# SH_SW1_V1_0.net
KiCad netlist of a schematic drawn in Altium Designer
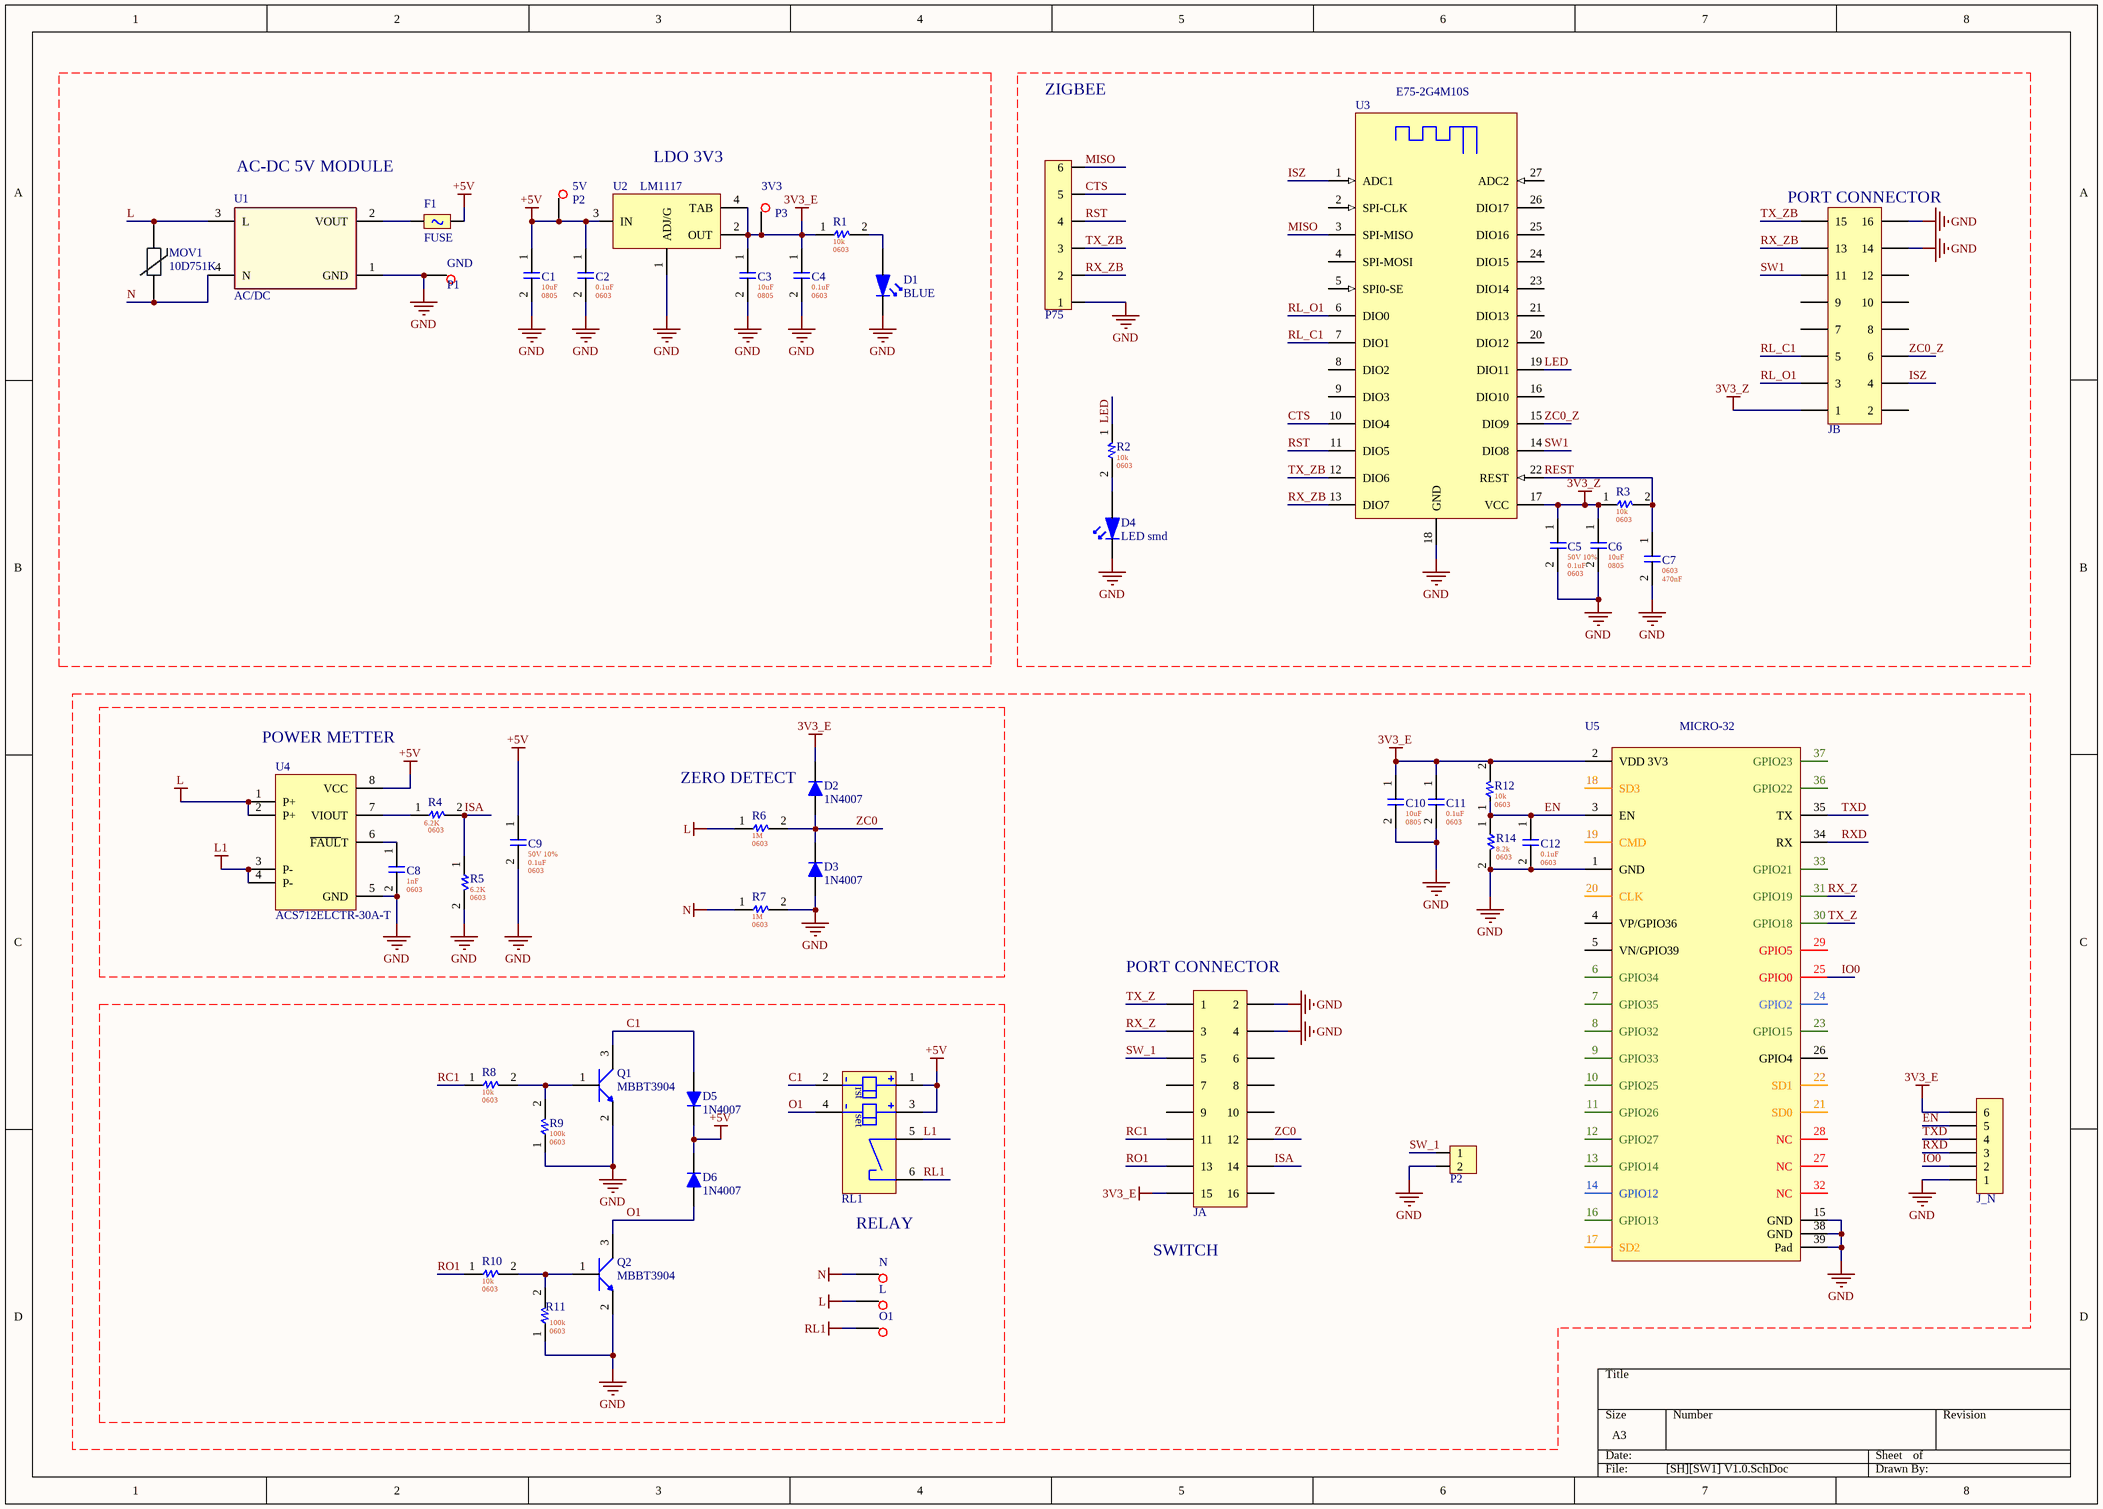
[diagram p0: [SH][SW1] V1.0.SchDoc]

(export (version "E")
  (design (tool "Eeschema 10.0.6"))
  (components
    (comp (ref "3V3") (value "P3") (footprint "TEXT_POINT") (libsource (lib "Kienlib") (part "P1")))
    (comp (ref "5V") (value "P2") (footprint "TEXT_POINT") (libsource (lib "Kienlib") (part "P1")))
    (comp (ref "C1")
      (value "10uF")
      (footprint "0805 C")
      (description "CAP CER 10uF 50V 10% 0805 SMD")
      (fields (field (name "FP") "0805") (field (name "CREATOR") "MMUOP"))
      (libsource (lib "Capacitor") (part "0805 10uF CER"))
    )
    (comp (ref "C2")
      (value "0.1uF")
      (footprint "0603 C")
      (description "CAP CER 0.1uF 50V 10% 0603 SMD")
      (fields (field (name "FP") "0603") (field (name "CREATOR") "MMUOP"))
      (libsource (lib "Capacitor") (part "0603 0.1uF CER"))
    )
    (comp (ref "C3")
      (value "10uF")
      (footprint "0805 C")
      (description "CAP CER 10uF 50V 10% 0805 SMD")
      (fields (field (name "FP") "0805") (field (name "CREATOR") "MMUOP"))
      (libsource (lib "Capacitor") (part "0805 10uF CER"))
    )
    (comp (ref "C4")
      (value "0.1uF")
      (footprint "0603 C")
      (description "CAP CER 0.1uF 50V 10% 0603 SMD")
      (fields (field (name "FP") "0603") (field (name "CREATOR") "MMUOP"))
      (libsource (lib "Capacitor") (part "0603 0.1uF CER"))
    )
    (comp (ref "C5")
      (value "0.1uF")
      (footprint "0603 C")
      (description "CAP CER 0.1uF 50V 10% 0603 SMD")
      (fields
        (field (name "VOLTAGE + TOLE") "50V 10%")
        (field (name "FP") "0603")
        (field (name "CREATOR") "MMUOP")
      )
      (libsource (lib "Capacitor") (part "0603 0.1uF CER"))
    )
    (comp (ref "C6")
      (value "10uF")
      (footprint "0805 C")
      (description "CAP CER 10uF 50V 10% 0805 SMD")
      (fields (field (name "FP") "0805") (field (name "CREATOR") "MMUOP"))
      (libsource (lib "Capacitor") (part "0805 10uF CER"))
    )
    (comp (ref "C7")
      (value "470nF")
      (footprint "0603 C")
      (description "CAP CER 470nF 50V 10% 0603 SMD")
      (fields (field (name "FP") "0603") (field (name "CREATOR") "MMUOP"))
      (libsource (lib "Capacitor") (part "0603 470nF CER"))
    )
    (comp (ref "C8")
      (value "1nF")
      (footprint "0603 C")
      (description "CAP CER 1nF 50V 10% 0603 SMD")
      (fields (field (name "FP") "0603") (field (name "CREATOR") "MMUOP"))
      (libsource (lib "Capacitor") (part "0603 1nF CER"))
    )
    (comp (ref "C9")
      (value "0.1uF")
      (footprint "0603 C")
      (description "CAP CER 0.1uF 50V 10% 0603 SMD")
      (fields
        (field (name "VOLTAGE + TOLE") "50V 10%")
        (field (name "FP") "0603")
        (field (name "CREATOR") "MMUOP")
      )
      (libsource (lib "Capacitor") (part "0603 0.1uF CER"))
    )
    (comp (ref "C10")
      (value "10uF")
      (footprint "0805 C")
      (description "CAP CER 10uF 50V 10% 0805 SMD")
      (fields (field (name "FP") "0805") (field (name "CREATOR") "MMUOP"))
      (libsource (lib "Capacitor") (part "0805 10uF CER"))
    )
    (comp (ref "C11")
      (value "0.1uF")
      (footprint "0603 C")
      (description "CAP CER 0.1uF 50V 10% 0603 SMD")
      (fields (field (name "FP") "0603") (field (name "CREATOR") "MMUOP"))
      (libsource (lib "Capacitor") (part "0603 0.1uF CER"))
    )
    (comp (ref "C12")
      (value "0.1uF")
      (footprint "0603 C")
      (description "CAP CER 0.1uF 50V 10% 0603 SMD")
      (fields (field (name "FP") "0603") (field (name "CREATOR") "MMUOP"))
      (libsource (lib "Capacitor") (part "0603 0.1uF CER"))
    )
    (comp (ref "D1") (value "BLUE") (footprint "Led 1206") (libsource (lib "Kienlib") (part "LED smd")))
    (comp (ref "D2")
      (value "1N4007")
      (footprint "SOD-123")
      (libsource (lib "Kienlib") (part "Diode schottky"))
    )
    (comp (ref "D3")
      (value "1N4007")
      (footprint "SOD-123")
      (libsource (lib "Kienlib") (part "Diode schottky"))
    )
    (comp (ref "D4") (value "LED smd") (footprint "Led 1206") (libsource (lib "Kienlib") (part "LED smd")))
    (comp (ref "D5")
      (value "1N4007")
      (footprint "SOD-123")
      (libsource (lib "Kienlib") (part "Diode schottky"))
    )
    (comp (ref "D6")
      (value "1N4007")
      (footprint "SOD-123")
      (libsource (lib "Kienlib") (part "Diode schottky"))
    )
    (comp (ref "F1") (value "FUSE") (footprint "1812") (libsource (lib "Kienlib") (part "FUSE")))
    (comp (ref "GND") (value "P1") (footprint "TEXT_POINT") (libsource (lib "Kienlib") (part "P1")))
    (comp (ref "JA")
      (value "rao doi")
      (footprint "P2X8 - 2.0mm - female - SMD")
      (libsource (lib "Kienlib") (part "P2x8"))
    )
    (comp (ref "JB") (value "rao doi") (footprint "P2X8 - 2.0mm - SMD") (libsource (lib "") (part "P2x8_1")))
    (comp (ref "J_N") (value "P6") (footprint "P6 - 1.27MM") (libsource (lib "Kienlib") (part "P6")))
    (comp (ref "L") (value "P1") (footprint "P1 - BRASS TERMINAL") (libsource (lib "Kienlib") (part "P1")))
    (comp (ref "MOV1")
      (value "10D751K")
      (footprint "MOV")
      (description "750V")
      (libsource (lib "Kienlib") (part "VARISTOR"))
    )
    (comp (ref "N") (value "P1") (footprint "P1 - BRASS TERMINAL") (libsource (lib "Kienlib") (part "P1")))
    (comp (ref "O1") (value "P1") (footprint "P1 - BRASS TERMINAL") (libsource (lib "Kienlib") (part "P1")))
    (comp (ref "P2") (value "P2") (footprint "P2 - 2.54mm") (libsource (lib "Kienlib") (part "P2")))
    (comp (ref "P75") (value "P6") (footprint "P6 - 1.27MM") (libsource (lib "") (part "P6_1")))
    (comp (ref "Q1")
      (value "MBBT3904")
      (footprint "SOT 23-3")
      (description "Bipolar (BJT) Transistor NPN 40 V 200 mA 300MHz 350 mW Surface Mount SOT-23-3 (TO-236)")
      (libsource (lib "Kienlib") (part "TRANS NPN"))
    )
    (comp (ref "Q2")
      (value "MBBT3904")
      (footprint "SOT 23-3")
      (description "Bipolar (BJT) Transistor NPN 40 V 200 mA 300MHz 350 mW Surface Mount SOT-23-3 (TO-236)")
      (libsource (lib "Kienlib") (part "TRANS NPN"))
    )
    (comp (ref "R1")
      (value "10k")
      (footprint "0603 R")
      (description "10k 1% 0603 SMD")
      (fields (field (name "FP") "0603") (field (name "CREATOR") "MMUOP"))
      (libsource (lib "Res") (part "0603 10k 1%"))
    )
    (comp (ref "R2")
      (value "10k")
      (footprint "0603 R")
      (description "10k 1% 0603 SMD")
      (fields (field (name "FP") "0603") (field (name "CREATOR") "MMUOP"))
      (libsource (lib "Res") (part "0603 10k 1%"))
    )
    (comp (ref "R3")
      (value "10k")
      (footprint "0603 R")
      (description "10k 1% 0603 SMD")
      (fields (field (name "FP") "0603") (field (name "CREATOR") "MMUOP"))
      (libsource (lib "Res") (part "0603 10k 1%"))
    )
    (comp (ref "R4")
      (value "6.2K")
      (footprint "0603 R")
      (description "8.2k 1% 0603 SMD")
      (fields (field (name "FP") "0603") (field (name "Comment") "8.2k") (field (name "CREATOR") "MMUOP"))
      (libsource (lib "Res") (part "0603 8.2k 1%"))
    )
    (comp (ref "R5")
      (value "6.2K")
      (footprint "0603 R")
      (description "8.2k 1% 0603 SMD")
      (fields (field (name "FP") "0603") (field (name "Comment") "8.2k") (field (name "CREATOR") "MMUOP"))
      (libsource (lib "Res") (part "0603 8.2k 1%"))
    )
    (comp (ref "R6")
      (value "1M")
      (footprint "0603 R")
      (description "1M 1% 0603 SMD")
      (fields (field (name "FP") "0603") (field (name "CREATOR") "MMUOP"))
      (libsource (lib "Res") (part "0603 1M 1%"))
    )
    (comp (ref "R7")
      (value "1M")
      (footprint "0603 R")
      (description "1M 1% 0603 SMD")
      (fields (field (name "FP") "0603") (field (name "CREATOR") "MMUOP"))
      (libsource (lib "Res") (part "0603 1M 1%"))
    )
    (comp (ref "R8")
      (value "10k")
      (footprint "0603 R")
      (description "10k 1% 0603 SMD")
      (fields (field (name "FP") "0603") (field (name "Comment") "10K") (field (name "CREATOR") "MMUOP"))
      (libsource (lib "Res") (part "0603 10k 1%"))
    )
    (comp (ref "R9")
      (value "100k")
      (footprint "0603 R")
      (description "100k 1% 0603 SMD")
      (fields (field (name "FP") "0603") (field (name "CREATOR") "MMUOP"))
      (libsource (lib "Res") (part "0603 100k 1%"))
    )
    (comp (ref "R10")
      (value "10k")
      (footprint "0603 R")
      (description "10k 1% 0603 SMD")
      (fields (field (name "FP") "0603") (field (name "Comment") "10K") (field (name "CREATOR") "MMUOP"))
      (libsource (lib "Res") (part "0603 10k 1%"))
    )
    (comp (ref "R11")
      (value "100k")
      (footprint "0603 R")
      (description "100k 1% 0603 SMD")
      (fields (field (name "FP") "0603") (field (name "CREATOR") "MMUOP"))
      (libsource (lib "Res") (part "0603 100k 1%"))
    )
    (comp (ref "R12")
      (value "10k")
      (footprint "0603 R")
      (description "10k 1% 0603 SMD")
      (fields (field (name "FP") "0603") (field (name "CREATOR") "MMUOP"))
      (libsource (lib "Res") (part "0603 10k 1%"))
    )
    (comp (ref "R14")
      (value "8.2k")
      (footprint "0603 R")
      (description "8.2k 1% 0603 SMD")
      (fields (field (name "FP") "0603") (field (name "CREATOR") "MMUOP"))
      (libsource (lib "Res") (part "0603 8.2k 1%"))
    )
    (comp (ref "RL1")
      (value "RELAY CHOT")
      (footprint "HFE60")
      (libsource (lib "Kienlib") (part "RELAY CHOT"))
    )
    (comp (ref "U1") (value "AC/DC") (footprint "AC-DC 5V K4H24") (libsource (lib "Kienlib") (part "AC/DC")))
    (comp (ref "U2") (value "LM1117") (footprint "SOT23-4") (libsource (lib "Kienlib") (part "LM1117")))
    (comp (ref "U3")
      (value "E75-2G4M10S")
      (footprint "ebyte - E75-2G4M10S")
      (libsource (lib "Kienlib") (part "ebyte - E75-2G4M10S"))
    )
    (comp (ref "U4")
      (value "ACS712ELCTR-30A-T")
      (footprint "SOIC 8")
      (description "ACS712ELCTR-20A  SOIC 8")
      (libsource (lib "Kienlib") (part "ACS71240"))
    )
    (comp (ref "U5")
      (value "MICRO-32")
      (footprint "ESP MICRO 32")
      (libsource (lib "Kienlib") (part "ESP MICRO-32_FIX"))
    )
  )
  (nets
    (net (code "1") (name "+5V") (class "Default")
      (node (ref "5V") (pin "1") (pinfunction "P_1") (pintype "passive"))
      (node (ref "C1") (pin "1") (pinfunction "1_1") (pintype "passive"))
      (node (ref "C2") (pin "1") (pinfunction "1_1") (pintype "passive"))
      (node (ref "C9") (pin "1") (pinfunction "1_1") (pintype "passive"))
      (node (ref "D5") (pin "2") (pinfunction "2_2") (pintype "passive"))
      (node (ref "D6") (pin "2") (pinfunction "2_2") (pintype "passive"))
      (node (ref "F1") (pin "2") (pinfunction "2_2") (pintype "passive"))
      (node (ref "RL1") (pin "1") (pinfunction "1_1") (pintype "passive"))
      (node (ref "RL1") (pin "3") (pinfunction "3_3") (pintype "passive"))
      (node (ref "U2") (pin "3") (pinfunction "IN_3") (pintype "passive"))
      (node (ref "U4") (pin "8") (pinfunction "VCC_8") (pintype "passive"))
    )
    (net (code "2") (name "/C1") (class "Default")
      (node (ref "D5") (pin "1") (pinfunction "1_1") (pintype "passive"))
      (node (ref "Q1") (pin "3") (pinfunction "C_3") (pintype "passive"))
      (node (ref "RL1") (pin "2") (pinfunction "2_2") (pintype "passive"))
    )
    (net (code "3") (name "/CTS") (class "Default")
      (node (ref "P75") (pin "5") (pinfunction "5_5") (pintype "passive"))
      (node (ref "U3") (pin "10") (pinfunction "DIO4_10") (pintype "passive"))
    )
    (net (code "4") (name "/EN") (class "Default")
      (node (ref "C12") (pin "1") (pinfunction "1_1") (pintype "passive"))
      (node (ref "J_N") (pin "5") (pinfunction "5_5") (pintype "passive"))
      (node (ref "R12") (pin "1") (pinfunction "1_1") (pintype "passive"))
      (node (ref "R14") (pin "1") (pinfunction "1_1") (pintype "passive"))
      (node (ref "U5") (pin "3") (pinfunction "EN_3") (pintype "passive"))
    )
    (net (code "5") (name "/IO0") (class "Default")
      (node (ref "J_N") (pin "2") (pinfunction "2_2") (pintype "passive"))
      (node (ref "U5") (pin "25") (pinfunction "GPIO0_25") (pintype "passive"))
    )
    (net (code "6") (name "/ISA") (class "Default")
      (node (ref "JA") (pin "14") (pinfunction "14_14") (pintype "passive"))
      (node (ref "R4") (pin "2") (pinfunction "2_2") (pintype "passive"))
      (node (ref "R5") (pin "1") (pinfunction "1_1") (pintype "passive"))
    )
    (net (code "7") (name "/ISZ") (class "Default")
      (node (ref "JB") (pin "4") (pinfunction "4_4") (pintype "passive"))
      (node (ref "U3") (pin "1") (pinfunction "ADC1_1") (pintype "input"))
    )
    (net (code "8") (name "/LED") (class "Default")
      (node (ref "R2") (pin "1") (pinfunction "1_1") (pintype "passive"))
      (node (ref "U3") (pin "19") (pinfunction "DIO11_19") (pintype "passive"))
    )
    (net (code "9") (name "/MISO") (class "Default")
      (node (ref "P75") (pin "6") (pinfunction "6_6") (pintype "passive"))
      (node (ref "U3") (pin "3") (pinfunction "SPI-MISO_3") (pintype "passive"))
    )
    (net (code "10") (name "/O1") (class "Default")
      (node (ref "D6") (pin "1") (pinfunction "1_1") (pintype "passive"))
      (node (ref "Q2") (pin "3") (pinfunction "C_3") (pintype "passive"))
      (node (ref "RL1") (pin "4") (pinfunction "4_4") (pintype "passive"))
    )
    (net (code "11") (name "/RC1") (class "Default")
      (node (ref "JA") (pin "11") (pinfunction "11_11") (pintype "passive"))
      (node (ref "R8") (pin "1") (pinfunction "1_1") (pintype "passive"))
    )
    (net (code "12") (name "/REST") (class "Default")
      (node (ref "C7") (pin "1") (pinfunction "1_1") (pintype "passive"))
      (node (ref "R3") (pin "2") (pinfunction "2_2") (pintype "passive"))
      (node (ref "U3") (pin "22") (pinfunction "REST_22") (pintype "input"))
    )
    (net (code "13") (name "/RL_C1") (class "Default")
      (node (ref "JB") (pin "5") (pinfunction "5_5") (pintype "passive"))
      (node (ref "U3") (pin "7") (pinfunction "DIO1_7") (pintype "passive"))
    )
    (net (code "14") (name "/RL_O1") (class "Default")
      (node (ref "JB") (pin "3") (pinfunction "3_3") (pintype "passive"))
      (node (ref "U3") (pin "6") (pinfunction "DIO0_6") (pintype "passive"))
    )
    (net (code "15") (name "/RO1") (class "Default")
      (node (ref "JA") (pin "13") (pinfunction "13_13") (pintype "passive"))
      (node (ref "R10") (pin "1") (pinfunction "1_1") (pintype "passive"))
    )
    (net (code "16") (name "/RST") (class "Default")
      (node (ref "P75") (pin "4") (pinfunction "4_4") (pintype "passive"))
      (node (ref "U3") (pin "11") (pinfunction "DIO5_11") (pintype "passive"))
    )
    (net (code "17") (name "/RXD") (class "Default")
      (node (ref "J_N") (pin "3") (pinfunction "3_3") (pintype "passive"))
      (node (ref "U5") (pin "34") (pinfunction "RX_34") (pintype "passive"))
    )
    (net (code "18") (name "/RX_Z") (class "Default")
      (node (ref "JA") (pin "3") (pinfunction "3_3") (pintype "passive"))
      (node (ref "U5") (pin "31") (pinfunction "GPIO19_31") (pintype "passive"))
    )
    (net (code "19") (name "/RX_ZB") (class "Default")
      (node (ref "JB") (pin "13") (pinfunction "13_13") (pintype "passive"))
      (node (ref "P75") (pin "2") (pinfunction "2_2") (pintype "passive"))
      (node (ref "U3") (pin "13") (pinfunction "DIO7_13") (pintype "passive"))
    )
    (net (code "20") (name "/SW1") (class "Default")
      (node (ref "JB") (pin "11") (pinfunction "11_11") (pintype "passive"))
      (node (ref "U3") (pin "14") (pinfunction "DIO8_14") (pintype "passive"))
    )
    (net (code "21") (name "/SW_1") (class "Default")
      (node (ref "JA") (pin "5") (pinfunction "5_5") (pintype "passive"))
      (node (ref "P2") (pin "1") (pinfunction "1_1") (pintype "passive"))
    )
    (net (code "22") (name "/TXD") (class "Default")
      (node (ref "J_N") (pin "4") (pinfunction "4_4") (pintype "passive"))
      (node (ref "U5") (pin "35") (pinfunction "TX_35") (pintype "passive"))
    )
    (net (code "23") (name "/TX_Z") (class "Default")
      (node (ref "JA") (pin "1") (pinfunction "1_1") (pintype "passive"))
      (node (ref "U5") (pin "30") (pinfunction "GPIO18_30") (pintype "passive"))
    )
    (net (code "24") (name "/TX_ZB") (class "Default")
      (node (ref "JB") (pin "15") (pinfunction "15_15") (pintype "passive"))
      (node (ref "P75") (pin "3") (pinfunction "3_3") (pintype "passive"))
      (node (ref "U3") (pin "12") (pinfunction "DIO6_12") (pintype "passive"))
    )
    (net (code "25") (name "/ZC0") (class "Default")
      (node (ref "D2") (pin "1") (pinfunction "1_1") (pintype "passive"))
      (node (ref "D3") (pin "2") (pinfunction "2_2") (pintype "passive"))
      (node (ref "JA") (pin "12") (pinfunction "12_12") (pintype "passive"))
      (node (ref "R6") (pin "2") (pinfunction "2_2") (pintype "passive"))
    )
    (net (code "26") (name "/ZC0_Z") (class "Default")
      (node (ref "JB") (pin "6") (pinfunction "6_6") (pintype "passive"))
      (node (ref "U3") (pin "15") (pinfunction "DIO9_15") (pintype "passive"))
    )
    (net (code "27") (name "3V3_E") (class "Default")
      (node (ref "3V3") (pin "1") (pinfunction "P_1") (pintype "passive"))
      (node (ref "C10") (pin "1") (pinfunction "1_1") (pintype "passive"))
      (node (ref "C11") (pin "1") (pinfunction "1_1") (pintype "passive"))
      (node (ref "C3") (pin "1") (pinfunction "1_1") (pintype "passive"))
      (node (ref "C4") (pin "1") (pinfunction "1_1") (pintype "passive"))
      (node (ref "D2") (pin "2") (pinfunction "2_2") (pintype "passive"))
      (node (ref "JA") (pin "15") (pinfunction "15_15") (pintype "passive"))
      (node (ref "J_N") (pin "6") (pinfunction "6_6") (pintype "passive"))
      (node (ref "R1") (pin "1") (pinfunction "1_1") (pintype "passive"))
      (node (ref "R12") (pin "2") (pinfunction "2_2") (pintype "passive"))
      (node (ref "U2") (pin "2") (pinfunction "OUT_2") (pintype "passive"))
      (node (ref "U2") (pin "4") (pinfunction "TAB_4") (pintype "passive"))
      (node (ref "U5") (pin "2") (pinfunction "VDD_3V3_2") (pintype "passive"))
    )
    (net (code "28") (name "3V3_Z") (class "Default")
      (node (ref "C5") (pin "1") (pinfunction "1_1") (pintype "passive"))
      (node (ref "C6") (pin "1") (pinfunction "1_1") (pintype "passive"))
      (node (ref "JB") (pin "1") (pinfunction "1_1") (pintype "passive"))
      (node (ref "R3") (pin "1") (pinfunction "1_1") (pintype "passive"))
      (node (ref "U3") (pin "17") (pinfunction "VCC_17") (pintype "passive"))
    )
    (net (code "29") (name "GND") (class "Default")
      (node (ref "C1") (pin "2") (pinfunction "2_2") (pintype "passive"))
      (node (ref "C10") (pin "2") (pinfunction "2_2") (pintype "passive"))
      (node (ref "C11") (pin "2") (pinfunction "2_2") (pintype "passive"))
      (node (ref "C12") (pin "2") (pinfunction "2_2") (pintype "passive"))
      (node (ref "C2") (pin "2") (pinfunction "2_2") (pintype "passive"))
      (node (ref "C3") (pin "2") (pinfunction "2_2") (pintype "passive"))
      (node (ref "C4") (pin "2") (pinfunction "2_2") (pintype "passive"))
      (node (ref "C5") (pin "2") (pinfunction "2_2") (pintype "passive"))
      (node (ref "C6") (pin "2") (pinfunction "2_2") (pintype "passive"))
      (node (ref "C7") (pin "2") (pinfunction "2_2") (pintype "passive"))
      (node (ref "C8") (pin "2") (pinfunction "2_2") (pintype "passive"))
      (node (ref "C9") (pin "2") (pinfunction "2_2") (pintype "passive"))
      (node (ref "D1") (pin "2") (pinfunction "2_2") (pintype "passive"))
      (node (ref "D3") (pin "1") (pinfunction "1_1") (pintype "passive"))
      (node (ref "D4") (pin "2") (pinfunction "2_2") (pintype "passive"))
      (node (ref "GND") (pin "1") (pinfunction "P_1") (pintype "passive"))
      (node (ref "JA") (pin "2") (pinfunction "2_2") (pintype "passive"))
      (node (ref "JA") (pin "4") (pinfunction "4_4") (pintype "passive"))
      (node (ref "JB") (pin "14") (pinfunction "14_14") (pintype "passive"))
      (node (ref "JB") (pin "16") (pinfunction "16_16") (pintype "passive"))
      (node (ref "J_N") (pin "1") (pinfunction "1_1") (pintype "passive"))
      (node (ref "P2") (pin "2") (pinfunction "2_2") (pintype "passive"))
      (node (ref "P75") (pin "1") (pinfunction "1_1") (pintype "passive"))
      (node (ref "Q1") (pin "2") (pinfunction "E_2") (pintype "passive"))
      (node (ref "Q2") (pin "2") (pinfunction "E_2") (pintype "passive"))
      (node (ref "R11") (pin "1") (pinfunction "1_1") (pintype "passive"))
      (node (ref "R14") (pin "2") (pinfunction "2_2") (pintype "passive"))
      (node (ref "R5") (pin "2") (pinfunction "2_2") (pintype "passive"))
      (node (ref "R7") (pin "2") (pinfunction "2_2") (pintype "passive"))
      (node (ref "R9") (pin "1") (pinfunction "1_1") (pintype "passive"))
      (node (ref "U1") (pin "1") (pinfunction "GND_1") (pintype "passive"))
      (node (ref "U2") (pin "1") (pinfunction "ADJ/G_1") (pintype "passive"))
      (node (ref "U3") (pin "18") (pinfunction "GND_18") (pintype "passive"))
      (node (ref "U4") (pin "5") (pinfunction "GND_5") (pintype "passive"))
      (node (ref "U5") (pin "1") (pinfunction "GND_1") (pintype "passive"))
      (node (ref "U5") (pin "15") (pinfunction "GND_15") (pintype "passive"))
      (node (ref "U5") (pin "38") (pinfunction "GND_38") (pintype "passive"))
      (node (ref "U5") (pin "39") (pinfunction "Pad_39") (pintype "passive"))
    )
    (net (code "30") (name "L") (class "Default")
      (node (ref "L") (pin "1") (pinfunction "P_1") (pintype "passive"))
      (node (ref "MOV1") (pin "2") (pinfunction "2_2") (pintype "passive"))
      (node (ref "R6") (pin "1") (pinfunction "1_1") (pintype "passive"))
      (node (ref "U1") (pin "3") (pinfunction "L_3") (pintype "passive"))
      (node (ref "U4") (pin "1") (pinfunction "P+_1") (pintype "passive"))
      (node (ref "U4") (pin "2") (pinfunction "P+_2") (pintype "passive"))
    )
    (net (code "31") (name "L1") (class "Default")
      (node (ref "RL1") (pin "5") (pinfunction "5_5") (pintype "passive"))
      (node (ref "U4") (pin "3") (pinfunction "P-_3") (pintype "passive"))
      (node (ref "U4") (pin "4") (pinfunction "P-_4") (pintype "passive"))
    )
    (net (code "32") (name "N") (class "Default")
      (node (ref "MOV1") (pin "1") (pinfunction "1_1") (pintype "passive"))
      (node (ref "N") (pin "1") (pinfunction "P_1") (pintype "passive"))
      (node (ref "R7") (pin "1") (pinfunction "1_1") (pintype "passive"))
      (node (ref "U1") (pin "4") (pinfunction "N_4") (pintype "passive"))
    )
    (net (code "33") (name "Net-(D1-Pad1)") (class "Default")
      (node (ref "D1") (pin "1") (pinfunction "1_1") (pintype "passive"))
      (node (ref "R1") (pin "2") (pinfunction "2_2") (pintype "passive"))
    )
    (net (code "34") (name "Net-(D4-Pad1)") (class "Default")
      (node (ref "D4") (pin "1") (pinfunction "1_1") (pintype "passive"))
      (node (ref "R2") (pin "2") (pinfunction "2_2") (pintype "passive"))
    )
    (net (code "35") (name "Net-(Q1-B)") (class "Default")
      (node (ref "Q1") (pin "1") (pinfunction "B_1") (pintype "passive"))
      (node (ref "R8") (pin "2") (pinfunction "2_2") (pintype "passive"))
      (node (ref "R9") (pin "2") (pinfunction "2_2") (pintype "passive"))
    )
    (net (code "36") (name "Net-(Q2-B)") (class "Default")
      (node (ref "Q2") (pin "1") (pinfunction "B_1") (pintype "passive"))
      (node (ref "R10") (pin "2") (pinfunction "2_2") (pintype "passive"))
      (node (ref "R11") (pin "2") (pinfunction "2_2") (pintype "passive"))
    )
    (net (code "37") (name "Net-(U1-VOUT)") (class "Default")
      (node (ref "F1") (pin "1") (pinfunction "1_1") (pintype "passive"))
      (node (ref "U1") (pin "2") (pinfunction "VOUT_2") (pintype "passive"))
    )
    (net (code "38") (name "Net-(U4-VIOUT)") (class "Default")
      (node (ref "R4") (pin "1") (pinfunction "1_1") (pintype "passive"))
      (node (ref "U4") (pin "7") (pinfunction "VIOUT_7") (pintype "passive"))
    )
    (net (code "39") (name "Net-(U4-~{FAUL}T)") (class "Default")
      (node (ref "C8") (pin "1") (pinfunction "1_1") (pintype "passive"))
      (node (ref "U4") (pin "6") (pinfunction "~{FAUL}T_6") (pintype "passive"))
    )
    (net (code "40") (name "RL1") (class "Default")
      (node (ref "O1") (pin "1") (pinfunction "P_1") (pintype "passive"))
      (node (ref "RL1") (pin "6") (pinfunction "6_6") (pintype "passive"))
    )
    (net (code "41") (name "unconnected-(JA-Pad6)") (class "Default")
      (node (ref "JA") (pin "6") (pinfunction "6_6") (pintype "passive"))
    )
    (net (code "42") (name "unconnected-(JA-Pad7)") (class "Default")
      (node (ref "JA") (pin "7") (pinfunction "7_7") (pintype "passive"))
    )
    (net (code "43") (name "unconnected-(JA-Pad8)") (class "Default")
      (node (ref "JA") (pin "8") (pinfunction "8_8") (pintype "passive"))
    )
    (net (code "44") (name "unconnected-(JA-Pad9)") (class "Default")
      (node (ref "JA") (pin "9") (pinfunction "9_9") (pintype "passive"))
    )
    (net (code "45") (name "unconnected-(JA-Pad10)") (class "Default")
      (node (ref "JA") (pin "10") (pinfunction "10_10") (pintype "passive"))
    )
    (net (code "46") (name "unconnected-(JA-Pad16)") (class "Default")
      (node (ref "JA") (pin "16") (pinfunction "16_16") (pintype "passive"))
    )
    (net (code "47") (name "unconnected-(JB-Pad2)") (class "Default")
      (node (ref "JB") (pin "2") (pinfunction "2_2") (pintype "passive"))
    )
    (net (code "48") (name "unconnected-(JB-Pad7)") (class "Default")
      (node (ref "JB") (pin "7") (pinfunction "7_7") (pintype "passive"))
    )
    (net (code "49") (name "unconnected-(JB-Pad8)") (class "Default")
      (node (ref "JB") (pin "8") (pinfunction "8_8") (pintype "passive"))
    )
    (net (code "50") (name "unconnected-(JB-Pad9)") (class "Default")
      (node (ref "JB") (pin "9") (pinfunction "9_9") (pintype "passive"))
    )
    (net (code "51") (name "unconnected-(JB-Pad10)") (class "Default")
      (node (ref "JB") (pin "10") (pinfunction "10_10") (pintype "passive"))
    )
    (net (code "52") (name "unconnected-(JB-Pad12)") (class "Default")
      (node (ref "JB") (pin "12") (pinfunction "12_12") (pintype "passive"))
    )
    (net (code "53") (name "unconnected-(U3-ADC2-Pad27)") (class "Default")
      (node (ref "U3") (pin "27") (pinfunction "ADC2_27") (pintype "input"))
    )
    (net (code "54") (name "unconnected-(U3-DIO2-Pad8)") (class "Default")
      (node (ref "U3") (pin "8") (pinfunction "DIO2_8") (pintype "passive"))
    )
    (net (code "55") (name "unconnected-(U3-DIO3-Pad9)") (class "Default")
      (node (ref "U3") (pin "9") (pinfunction "DIO3_9") (pintype "passive"))
    )
    (net (code "56") (name "unconnected-(U3-DIO10-Pad16)") (class "Default")
      (node (ref "U3") (pin "16") (pinfunction "DIO10_16") (pintype "passive"))
    )
    (net (code "57") (name "unconnected-(U3-DIO12-Pad20)") (class "Default")
      (node (ref "U3") (pin "20") (pinfunction "DIO12_20") (pintype "passive"))
    )
    (net (code "58") (name "unconnected-(U3-DIO13-Pad21)") (class "Default")
      (node (ref "U3") (pin "21") (pinfunction "DIO13_21") (pintype "passive"))
    )
    (net (code "59") (name "unconnected-(U3-DIO14-Pad23)") (class "Default")
      (node (ref "U3") (pin "23") (pinfunction "DIO14_23") (pintype "passive"))
    )
    (net (code "60") (name "unconnected-(U3-DIO15-Pad24)") (class "Default")
      (node (ref "U3") (pin "24") (pinfunction "DIO15_24") (pintype "passive"))
    )
    (net (code "61") (name "unconnected-(U3-DIO16-Pad25)") (class "Default")
      (node (ref "U3") (pin "25") (pinfunction "DIO16_25") (pintype "passive"))
    )
    (net (code "62") (name "unconnected-(U3-DIO17-Pad26)") (class "Default")
      (node (ref "U3") (pin "26") (pinfunction "DIO17_26") (pintype "passive"))
    )
    (net (code "63") (name "unconnected-(U3-SPI-CLK-Pad2)") (class "Default")
      (node (ref "U3") (pin "2") (pinfunction "SPI-CLK_2") (pintype "input"))
    )
    (net (code "64") (name "unconnected-(U3-SPI-MOSI-Pad4)") (class "Default")
      (node (ref "U3") (pin "4") (pinfunction "SPI-MOSI_4") (pintype "passive"))
    )
    (net (code "65") (name "unconnected-(U3-SPI0-SE-Pad5)") (class "Default")
      (node (ref "U3") (pin "5") (pinfunction "SPI0-SE_5") (pintype "input"))
    )
    (net (code "66") (name "unconnected-(U5-CLK-Pad20)") (class "Default")
      (node (ref "U5") (pin "20") (pinfunction "CLK_20") (pintype "passive"))
    )
    (net (code "67") (name "unconnected-(U5-CMD-Pad19)") (class "Default")
      (node (ref "U5") (pin "19") (pinfunction "CMD_19") (pintype "passive"))
    )
    (net (code "68") (name "unconnected-(U5-GPIO2-Pad24)") (class "Default")
      (node (ref "U5") (pin "24") (pinfunction "GPIO2_24") (pintype "passive"))
    )
    (net (code "69") (name "unconnected-(U5-GPIO4-Pad26)") (class "Default")
      (node (ref "U5") (pin "26") (pinfunction "GPIO4_26") (pintype "passive"))
    )
    (net (code "70") (name "unconnected-(U5-GPIO5-Pad29)") (class "Default")
      (node (ref "U5") (pin "29") (pinfunction "GPIO5_29") (pintype "passive"))
    )
    (net (code "71") (name "unconnected-(U5-GPIO12-Pad14)") (class "Default")
      (node (ref "U5") (pin "14") (pinfunction "GPIO12_14") (pintype "passive"))
    )
    (net (code "72") (name "unconnected-(U5-GPIO13-Pad16)") (class "Default")
      (node (ref "U5") (pin "16") (pinfunction "GPIO13_16") (pintype "passive"))
    )
    (net (code "73") (name "unconnected-(U5-GPIO14-Pad13)") (class "Default")
      (node (ref "U5") (pin "13") (pinfunction "GPIO14_13") (pintype "passive"))
    )
    (net (code "74") (name "unconnected-(U5-GPIO15-Pad23)") (class "Default")
      (node (ref "U5") (pin "23") (pinfunction "GPIO15_23") (pintype "passive"))
    )
    (net (code "75") (name "unconnected-(U5-GPIO21-Pad33)") (class "Default")
      (node (ref "U5") (pin "33") (pinfunction "GPIO21_33") (pintype "passive"))
    )
    (net (code "76") (name "unconnected-(U5-GPIO22-Pad36)") (class "Default")
      (node (ref "U5") (pin "36") (pinfunction "GPIO22_36") (pintype "passive"))
    )
    (net (code "77") (name "unconnected-(U5-GPIO23-Pad37)") (class "Default")
      (node (ref "U5") (pin "37") (pinfunction "GPIO23_37") (pintype "passive"))
    )
    (net (code "78") (name "unconnected-(U5-GPIO25-Pad10)") (class "Default")
      (node (ref "U5") (pin "10") (pinfunction "GPIO25_10") (pintype "passive"))
    )
    (net (code "79") (name "unconnected-(U5-GPIO26-Pad11)") (class "Default")
      (node (ref "U5") (pin "11") (pinfunction "GPIO26_11") (pintype "passive"))
    )
    (net (code "80") (name "unconnected-(U5-GPIO27-Pad12)") (class "Default")
      (node (ref "U5") (pin "12") (pinfunction "GPIO27_12") (pintype "passive"))
    )
    (net (code "81") (name "unconnected-(U5-GPIO32-Pad8)") (class "Default")
      (node (ref "U5") (pin "8") (pinfunction "GPIO32_8") (pintype "passive"))
    )
    (net (code "82") (name "unconnected-(U5-GPIO33-Pad9)") (class "Default")
      (node (ref "U5") (pin "9") (pinfunction "GPIO33_9") (pintype "passive"))
    )
    (net (code "83") (name "unconnected-(U5-GPIO34-Pad6)") (class "Default")
      (node (ref "U5") (pin "6") (pinfunction "GPIO34_6") (pintype "passive"))
    )
    (net (code "84") (name "unconnected-(U5-GPIO35-Pad7)") (class "Default")
      (node (ref "U5") (pin "7") (pinfunction "GPIO35_7") (pintype "passive"))
    )
    (net (code "85") (name "unconnected-(U5-NC-Pad27)") (class "Default")
      (node (ref "U5") (pin "27") (pinfunction "NC_27") (pintype "passive"))
    )
    (net (code "86") (name "unconnected-(U5-NC-Pad28)") (class "Default")
      (node (ref "U5") (pin "28") (pinfunction "NC_28") (pintype "passive"))
    )
    (net (code "87") (name "unconnected-(U5-NC-Pad32)") (class "Default")
      (node (ref "U5") (pin "32") (pinfunction "NC_32") (pintype "passive"))
    )
    (net (code "88") (name "unconnected-(U5-SD0-Pad21)") (class "Default")
      (node (ref "U5") (pin "21") (pinfunction "SD0_21") (pintype "passive"))
    )
    (net (code "89") (name "unconnected-(U5-SD1-Pad22)") (class "Default")
      (node (ref "U5") (pin "22") (pinfunction "SD1_22") (pintype "passive"))
    )
    (net (code "90") (name "unconnected-(U5-SD2-Pad17)") (class "Default")
      (node (ref "U5") (pin "17") (pinfunction "SD2_17") (pintype "passive"))
    )
    (net (code "91") (name "unconnected-(U5-SD3-Pad18)") (class "Default")
      (node (ref "U5") (pin "18") (pinfunction "SD3_18") (pintype "passive"))
    )
    (net (code "92") (name "unconnected-(U5-VN{slash}GPIO39-Pad5)") (class "Default")
      (node (ref "U5") (pin "5") (pinfunction "VN/GPIO39_5") (pintype "passive"))
    )
    (net (code "93") (name "unconnected-(U5-VP{slash}GPIO36-Pad4)") (class "Default")
      (node (ref "U5") (pin "4") (pinfunction "VP/GPIO36_4") (pintype "passive"))
    )
  )
)
